# MSP-EXP430FR5739_1_1_4.net
KiCad netlist of a schematic drawn in EAGLE
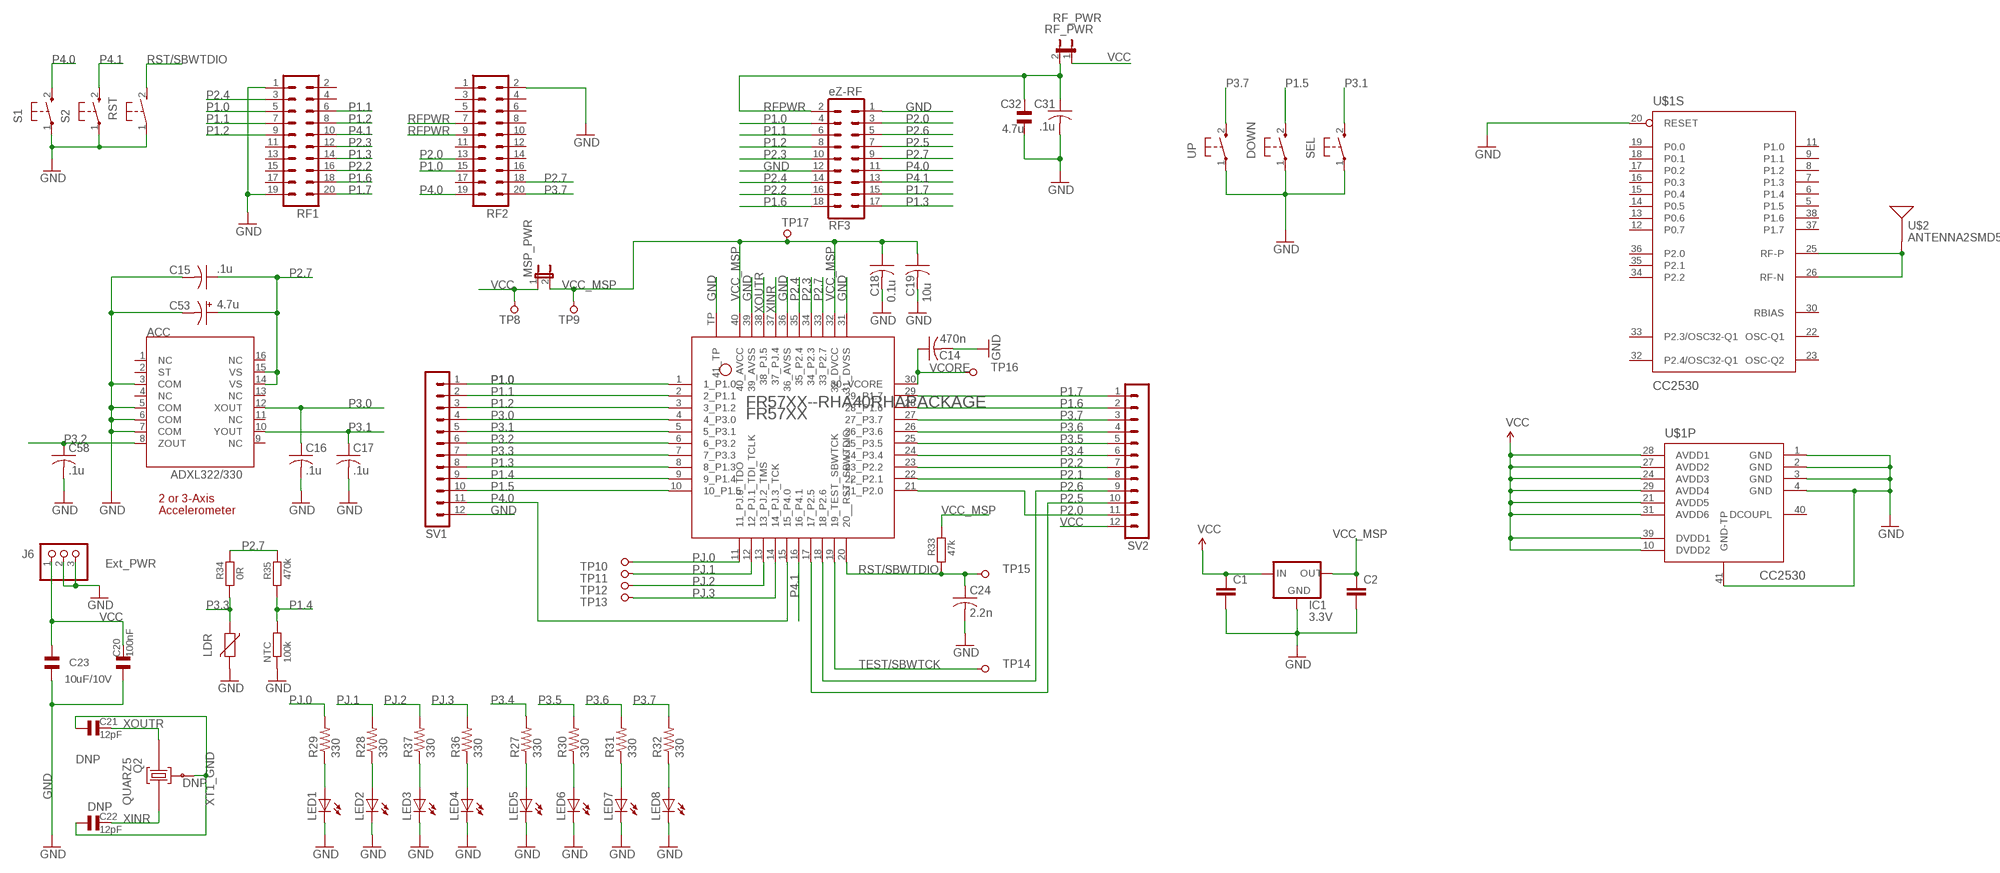
[diagram p0: schematic, sheet 1]

(export (version "E")
  (design (tool "Eeschema 10.0.6"))
  (components
    (comp (ref "ACC")
      (value "ADXL322/330")
      (footprint "eagle-import:RSA16")
      (libsource (lib "eagle-import") (part "ADXL330"))
    )
    (comp (ref "C1")
      (value "CAPPTH1")
      (footprint "eagle-import:CAP-PTH-5MM")
      (libsource (lib "eagle-import") (part "CAPPTH1"))
    )
    (comp (ref "C2")
      (value "CAPPTH1")
      (footprint "eagle-import:CAP-PTH-5MM")
      (libsource (lib "eagle-import") (part "CAPPTH1"))
    )
    (comp (ref "C14")
      (value "470n")
      (footprint "eagle-import:C0603")
      (libsource (lib "eagle-import") (part "C-USC0603"))
    )
    (comp (ref "C15")
      (value ".1u")
      (footprint "eagle-import:C0603")
      (libsource (lib "eagle-import") (part "C-USC0603"))
    )
    (comp (ref "C16")
      (value ".1u")
      (footprint "eagle-import:C0603")
      (libsource (lib "eagle-import") (part "C-USC0603"))
    )
    (comp (ref "C17")
      (value ".1u")
      (footprint "eagle-import:C0603")
      (libsource (lib "eagle-import") (part "C-USC0603"))
    )
    (comp (ref "C18")
      (value "0.1u")
      (footprint "eagle-import:C0603")
      (libsource (lib "eagle-import") (part "C-USC0603"))
    )
    (comp (ref "C19")
      (value "10u")
      (footprint "eagle-import:C0603")
      (libsource (lib "eagle-import") (part "C-USC0603"))
    )
    (comp (ref "C20")
      (value "100nF")
      (footprint "eagle-import:0603")
      (libsource (lib "eagle-import") (part "C_SMD0603"))
    )
    (comp (ref "C21")
      (value "12pF")
      (footprint "eagle-import:0603")
      (libsource (lib "eagle-import") (part "C_SMD0603"))
    )
    (comp (ref "C22")
      (value "12pF")
      (footprint "eagle-import:0603")
      (libsource (lib "eagle-import") (part "C_SMD0603"))
    )
    (comp (ref "C23")
      (value "10uF/10V")
      (footprint "eagle-import:0805")
      (libsource (lib "eagle-import") (part "C_0805"))
    )
    (comp (ref "C24")
      (value "2.2n")
      (footprint "eagle-import:C0603")
      (libsource (lib "eagle-import") (part "C-USC0603"))
    )
    (comp (ref "C31")
      (value ".1u")
      (footprint "eagle-import:C0603")
      (libsource (lib "eagle-import") (part "C-USC0603"))
    )
    (comp (ref "C32")
      (value "4.7u")
      (footprint "eagle-import:CSMD0805")
      (libsource (lib "eagle-import") (part "CSMD0805"))
    )
    (comp (ref "C53")
      (value "4.7u")
      (footprint "eagle-import:SMC_A")
      (libsource (lib "eagle-import") (part "CPOL-USSMCA"))
    )
    (comp (ref "C58")
      (value ".1u")
      (footprint "eagle-import:C0603")
      (libsource (lib "eagle-import") (part "C-USC0603"))
    )
    (comp (ref "DOWN")
      (value "PB")
      (footprint "eagle-import:PBTH")
      (libsource (lib "eagle-import") (part "PB"))
    )
    (comp (ref "FR57XX")
      (value "FR57XX--RHA40RHAPACKAGE")
      (footprint "eagle-import:RHA40")
      (libsource (lib "eagle-import") (part "FR57XX--RHA40RHAPACKAGE"))
    )
    (comp (ref "IC1")
      (value "3.3V")
      (footprint "eagle-import:78LXX")
      (libsource (lib "eagle-import") (part "78LXX"))
    )
    (comp (ref "J6")
      (value "PINHD-1X3")
      (footprint "eagle-import:1X03")
      (libsource (lib "eagle-import") (part "PINHD-1X3"))
    )
    (comp (ref "LDR")
      (value "R3,4")
      (footprint "eagle-import:R-3,4")
      (libsource (lib "eagle-import") (part "R3,4"))
    )
    (comp (ref "LED1")
      (value "LEDCHIPLED_0603")
      (footprint "eagle-import:CHIPLED_0603")
      (libsource (lib "eagle-import") (part "LEDCHIPLED_0603"))
    )
    (comp (ref "LED2")
      (value "LEDCHIPLED_0603")
      (footprint "eagle-import:CHIPLED_0603")
      (libsource (lib "eagle-import") (part "LEDCHIPLED_0603"))
    )
    (comp (ref "LED3")
      (value "LEDCHIPLED_0603")
      (footprint "eagle-import:CHIPLED_0603")
      (libsource (lib "eagle-import") (part "LEDCHIPLED_0603"))
    )
    (comp (ref "LED4")
      (value "LEDCHIPLED_0603")
      (footprint "eagle-import:CHIPLED_0603")
      (libsource (lib "eagle-import") (part "LEDCHIPLED_0603"))
    )
    (comp (ref "LED5")
      (value "LEDCHIPLED_0603")
      (footprint "eagle-import:CHIPLED_0603")
      (libsource (lib "eagle-import") (part "LEDCHIPLED_0603"))
    )
    (comp (ref "LED6")
      (value "LEDCHIPLED_0603")
      (footprint "eagle-import:CHIPLED_0603")
      (libsource (lib "eagle-import") (part "LEDCHIPLED_0603"))
    )
    (comp (ref "LED7")
      (value "LEDCHIPLED_0603")
      (footprint "eagle-import:CHIPLED_0603")
      (libsource (lib "eagle-import") (part "LEDCHIPLED_0603"))
    )
    (comp (ref "LED8")
      (value "LEDCHIPLED_0603")
      (footprint "eagle-import:CHIPLED_0603")
      (libsource (lib "eagle-import") (part "LEDCHIPLED_0603"))
    )
    (comp (ref "MSP_PWR")
      (value "JP1E")
      (footprint "eagle-import:JP1")
      (libsource (lib "eagle-import") (part "JP1E"))
    )
    (comp (ref "NTC")
      (value "100k")
      (footprint "eagle-import:0805")
      (libsource (lib "eagle-import") (part "R_0805"))
    )
    (comp (ref "Q2")
      (value "QUARZ5")
      (footprint "eagle-import:QUARZ5")
      (libsource (lib "eagle-import") (part "QUARZ5"))
    )
    (comp (ref "R27")
      (value "330")
      (footprint "eagle-import:R0603")
      (libsource (lib "eagle-import") (part "R-US_R0603"))
    )
    (comp (ref "R28")
      (value "330")
      (footprint "eagle-import:R0603")
      (libsource (lib "eagle-import") (part "R-US_R0603"))
    )
    (comp (ref "R29")
      (value "330")
      (footprint "eagle-import:R0603")
      (libsource (lib "eagle-import") (part "R-US_R0603"))
    )
    (comp (ref "R30")
      (value "330")
      (footprint "eagle-import:R0603")
      (libsource (lib "eagle-import") (part "R-US_R0603"))
    )
    (comp (ref "R31")
      (value "330")
      (footprint "eagle-import:R0603")
      (libsource (lib "eagle-import") (part "R-US_R0603"))
    )
    (comp (ref "R32")
      (value "330")
      (footprint "eagle-import:R0603")
      (libsource (lib "eagle-import") (part "R-US_R0603"))
    )
    (comp (ref "R33")
      (value "47k")
      (footprint "eagle-import:0603")
      (libsource (lib "eagle-import") (part "R_SMDR0603"))
    )
    (comp (ref "R34")
      (value "0R")
      (footprint "eagle-import:0603")
      (libsource (lib "eagle-import") (part "R_SMDR0603"))
    )
    (comp (ref "R35")
      (value "470k")
      (footprint "eagle-import:0603")
      (libsource (lib "eagle-import") (part "R_SMDR0603"))
    )
    (comp (ref "R36")
      (value "330")
      (footprint "eagle-import:R0603")
      (libsource (lib "eagle-import") (part "R-US_R0603"))
    )
    (comp (ref "R37")
      (value "330")
      (footprint "eagle-import:R0603")
      (libsource (lib "eagle-import") (part "R-US_R0603"))
    )
    (comp (ref "RF1")
      (value "TFM-110-02-SM-D-A-K")
      (footprint "eagle-import:TFM-110-02-SM-D-A-K")
      (libsource (lib "eagle-import") (part "TFM-110-02-SM-D-A-K"))
    )
    (comp (ref "RF2")
      (value "TFM-110-02-SM-D-A-K")
      (footprint "eagle-import:TFM-110-02-SM-D-A-K")
      (libsource (lib "eagle-import") (part "TFM-110-02-SM-D-A-K"))
    )
    (comp (ref "RF3")
      (value "eZ-RF")
      (footprint "eagle-import:MA09-2")
      (libsource (lib "eagle-import") (part "MA09-2"))
    )
    (comp (ref "RF_PWR")
      (value "RF_PWR")
      (footprint "eagle-import:JP1")
      (libsource (lib "eagle-import") (part "JP1E"))
    )
    (comp (ref "RST")
      (value "EVQPPDASTD")
      (footprint "eagle-import:EVQPPDA")
      (libsource (lib "eagle-import") (part "EVQPPDASTD"))
    )
    (comp (ref "S1")
      (value "PB")
      (footprint "eagle-import:PBTH")
      (libsource (lib "eagle-import") (part "PB"))
    )
    (comp (ref "S2")
      (value "PB")
      (footprint "eagle-import:PBTH")
      (libsource (lib "eagle-import") (part "PB"))
    )
    (comp (ref "SEL")
      (value "PB")
      (footprint "eagle-import:PBTH")
      (libsource (lib "eagle-import") (part "PB"))
    )
    (comp (ref "SV1")
      (value "MA12-1")
      (footprint "eagle-import:MA12-1")
      (libsource (lib "eagle-import") (part "MA12-1"))
    )
    (comp (ref "SV2")
      (value "MA12-1")
      (footprint "eagle-import:MA12-1")
      (libsource (lib "eagle-import") (part "MA12-1"))
    )
    (comp (ref "TP8")
      (value "TP05TP10")
      (footprint "eagle-import:TP10")
      (libsource (lib "eagle-import") (part "TP05TP10"))
    )
    (comp (ref "TP9")
      (value "TP05TP10")
      (footprint "eagle-import:TP10")
      (libsource (lib "eagle-import") (part "TP05TP10"))
    )
    (comp (ref "TP10")
      (value "TP05TP10")
      (footprint "eagle-import:TP10")
      (libsource (lib "eagle-import") (part "TP05TP10"))
    )
    (comp (ref "TP11")
      (value "TP05TP10")
      (footprint "eagle-import:TP10")
      (libsource (lib "eagle-import") (part "TP05TP10"))
    )
    (comp (ref "TP12")
      (value "TP05TP10")
      (footprint "eagle-import:TP10")
      (libsource (lib "eagle-import") (part "TP05TP10"))
    )
    (comp (ref "TP13")
      (value "TP05TP10")
      (footprint "eagle-import:TP10")
      (libsource (lib "eagle-import") (part "TP05TP10"))
    )
    (comp (ref "TP14")
      (value "TP05TP10")
      (footprint "eagle-import:TP10")
      (libsource (lib "eagle-import") (part "TP05TP10"))
    )
    (comp (ref "TP15")
      (value "TP05TP10")
      (footprint "eagle-import:TP10")
      (libsource (lib "eagle-import") (part "TP05TP10"))
    )
    (comp (ref "TP16")
      (value "TP05TP10")
      (footprint "eagle-import:TP10")
      (libsource (lib "eagle-import") (part "TP05TP10"))
    )
    (comp (ref "TP17")
      (value "TP05TP10")
      (footprint "eagle-import:TP10")
      (libsource (lib "eagle-import") (part "TP05TP10"))
    )
    (comp (ref "U$1")
      (value "CC2530")
      (footprint "eagle-import:QFN50P600X600X100-41N")
      (libsource (lib "eagle-import") (part "CC2530"))
    )
    (comp (ref "U$2")
      (value "ANTENNA2SMD5")
      (footprint "eagle-import:ANTENNA-CHIP5")
      (libsource (lib "eagle-import") (part "ANTENNA2SMD5"))
    )
    (comp (ref "UP")
      (value "PB")
      (footprint "eagle-import:PBTH")
      (libsource (lib "eagle-import") (part "PB"))
    )
  )
  (nets
    (net (code "1") (name "/DCOUPL") (class "Default")
      (node (ref "U$1") (pin "40") (pinfunction "DCOUPL_40") (pintype "power_in"))
    )
    (net (code "2") (name "/P1.0") (class "Default")
      (node (ref "FR57XX") (pin "1") (pinfunction "1_P1.0_1") (pintype "passive"))
      (node (ref "RF1") (pin "5") (pinfunction "5_5") (pintype "passive"))
      (node (ref "RF2") (pin "15") (pinfunction "15_15") (pintype "passive"))
      (node (ref "RF3") (pin "4") (pinfunction "4_4") (pintype "passive"))
      (node (ref "SV1") (pin "1") (pinfunction "1_1") (pintype "passive"))
    )
    (net (code "3") (name "/P1.1") (class "Default")
      (node (ref "FR57XX") (pin "2") (pinfunction "2_P1.1_2") (pintype "passive"))
      (node (ref "RF1") (pin "6") (pinfunction "6_6") (pintype "passive"))
      (node (ref "RF1") (pin "7") (pinfunction "7_7") (pintype "passive"))
      (node (ref "RF3") (pin "6") (pinfunction "6_6") (pintype "passive"))
      (node (ref "SV1") (pin "2") (pinfunction "2_2") (pintype "passive"))
    )
    (net (code "4") (name "/P1.2") (class "Default")
      (node (ref "FR57XX") (pin "3") (pinfunction "3_P1.2_3") (pintype "passive"))
      (node (ref "RF1") (pin "8") (pinfunction "8_8") (pintype "passive"))
      (node (ref "RF1") (pin "9") (pinfunction "9_9") (pintype "passive"))
      (node (ref "RF3") (pin "8") (pinfunction "8_8") (pintype "passive"))
      (node (ref "SV1") (pin "3") (pinfunction "3_3") (pintype "passive"))
    )
    (net (code "5") (name "/P1.3") (class "Default")
      (node (ref "FR57XX") (pin "8") (pinfunction "8_P1.3_8") (pintype "passive"))
      (node (ref "RF1") (pin "14") (pinfunction "14_14") (pintype "passive"))
      (node (ref "RF3") (pin "17") (pinfunction "17_17") (pintype "passive"))
      (node (ref "SV1") (pin "8") (pinfunction "8_8") (pintype "passive"))
    )
    (net (code "6") (name "/P1.4") (class "Default")
      (node (ref "FR57XX") (pin "9") (pinfunction "9_P1.4_9") (pintype "passive"))
      (node (ref "NTC") (pin "2") (pinfunction "2_2") (pintype "passive"))
      (node (ref "R35") (pin "1") (pinfunction "1_1") (pintype "passive"))
      (node (ref "SV1") (pin "9") (pinfunction "9_9") (pintype "passive"))
    )
    (net (code "7") (name "/P1.5") (class "Default")
      (node (ref "DOWN") (pin "2") (pinfunction "S_2") (pintype "passive"))
      (node (ref "FR57XX") (pin "10") (pinfunction "10_P1.5_10") (pintype "passive"))
      (node (ref "SV1") (pin "10") (pinfunction "10_10") (pintype "passive"))
    )
    (net (code "8") (name "/P1.6") (class "Default")
      (node (ref "FR57XX") (pin "28") (pinfunction "28_P1.6_28") (pintype "passive"))
      (node (ref "RF1") (pin "18") (pinfunction "18_18") (pintype "passive"))
      (node (ref "RF3") (pin "18") (pinfunction "18_18") (pintype "passive"))
      (node (ref "SV2") (pin "2") (pinfunction "2_2") (pintype "passive"))
    )
    (net (code "9") (name "/P1.7") (class "Default")
      (node (ref "FR57XX") (pin "29") (pinfunction "29_P1.7_29") (pintype "passive"))
      (node (ref "RF1") (pin "20") (pinfunction "20_20") (pintype "passive"))
      (node (ref "RF3") (pin "15") (pinfunction "15_15") (pintype "passive"))
      (node (ref "SV2") (pin "1") (pinfunction "1_1") (pintype "passive"))
    )
    (net (code "10") (name "/P2.0") (class "Default")
      (node (ref "FR57XX") (pin "21") (pinfunction "21_P2.0_21") (pintype "passive"))
      (node (ref "RF2") (pin "13") (pinfunction "13_13") (pintype "passive"))
      (node (ref "RF3") (pin "3") (pinfunction "3_3") (pintype "passive"))
      (node (ref "SV2") (pin "11") (pinfunction "11_11") (pintype "passive"))
    )
    (net (code "11") (name "/P2.1") (class "Default")
      (node (ref "FR57XX") (pin "22") (pinfunction "22_P2.1_22") (pintype "passive"))
      (node (ref "SV2") (pin "8") (pinfunction "8_8") (pintype "passive"))
    )
    (net (code "12") (name "/P2.2") (class "Default")
      (node (ref "FR57XX") (pin "23") (pinfunction "23_P2.2_23") (pintype "passive"))
      (node (ref "RF1") (pin "16") (pinfunction "16_16") (pintype "passive"))
      (node (ref "RF3") (pin "16") (pinfunction "16_16") (pintype "passive"))
      (node (ref "SV2") (pin "7") (pinfunction "7_7") (pintype "passive"))
    )
    (net (code "13") (name "/P2.3") (class "Default")
      (node (ref "FR57XX") (pin "34") (pinfunction "34_P2.3_34") (pintype "passive"))
      (node (ref "RF1") (pin "12") (pinfunction "12_12") (pintype "passive"))
      (node (ref "RF3") (pin "10") (pinfunction "10_10") (pintype "passive"))
    )
    (net (code "14") (name "/P2.4") (class "Default")
      (node (ref "FR57XX") (pin "35") (pinfunction "35_P2.4_35") (pintype "passive"))
      (node (ref "RF1") (pin "3") (pinfunction "3_3") (pintype "passive"))
      (node (ref "RF3") (pin "14") (pinfunction "14_14") (pintype "passive"))
    )
    (net (code "15") (name "/P2.5") (class "Default")
      (node (ref "FR57XX") (pin "17") (pinfunction "17_P2.5_17") (pintype "passive"))
      (node (ref "RF3") (pin "7") (pinfunction "7_7") (pintype "passive"))
      (node (ref "SV2") (pin "10") (pinfunction "10_10") (pintype "passive"))
    )
    (net (code "16") (name "/P2.6") (class "Default")
      (node (ref "FR57XX") (pin "18") (pinfunction "18_P2.6_18") (pintype "passive"))
      (node (ref "RF3") (pin "5") (pinfunction "5_5") (pintype "passive"))
      (node (ref "SV2") (pin "9") (pinfunction "9_9") (pintype "passive"))
    )
    (net (code "17") (name "/P2.7") (class "Default")
      (node (ref "ACC") (pin "14") (pinfunction "VS_14") (pintype "bidirectional"))
      (node (ref "ACC") (pin "15") (pinfunction "VS_15") (pintype "bidirectional"))
      (node (ref "C15") (pin "1") (pinfunction "1_1") (pintype "passive"))
      (node (ref "C53") (pin "+") (pinfunction "+_+") (pintype "passive"))
      (node (ref "FR57XX") (pin "33") (pinfunction "33_P2.7_33") (pintype "passive"))
      (node (ref "R34") (pin "2") (pinfunction "2_2") (pintype "passive"))
      (node (ref "R35") (pin "2") (pinfunction "2_2") (pintype "passive"))
      (node (ref "RF2") (pin "18") (pinfunction "18_18") (pintype "passive"))
      (node (ref "RF3") (pin "9") (pinfunction "9_9") (pintype "passive"))
    )
    (net (code "18") (name "/P3.0") (class "Default")
      (node (ref "ACC") (pin "12") (pinfunction "XOUT_12") (pintype "bidirectional"))
      (node (ref "C16") (pin "1") (pinfunction "1_1") (pintype "passive"))
      (node (ref "FR57XX") (pin "4") (pinfunction "4_P3.0_4") (pintype "passive"))
      (node (ref "SV1") (pin "4") (pinfunction "4_4") (pintype "passive"))
    )
    (net (code "19") (name "/P3.1") (class "Default")
      (node (ref "ACC") (pin "10") (pinfunction "YOUT_10") (pintype "bidirectional"))
      (node (ref "C17") (pin "1") (pinfunction "1_1") (pintype "passive"))
      (node (ref "FR57XX") (pin "5") (pinfunction "5_P3.1_5") (pintype "passive"))
      (node (ref "SEL") (pin "2") (pinfunction "S_2") (pintype "passive"))
      (node (ref "SV1") (pin "5") (pinfunction "5_5") (pintype "passive"))
    )
    (net (code "20") (name "/P3.2") (class "Default")
      (node (ref "ACC") (pin "8") (pinfunction "ZOUT_8") (pintype "bidirectional"))
      (node (ref "C58") (pin "1") (pinfunction "1_1") (pintype "passive"))
      (node (ref "FR57XX") (pin "6") (pinfunction "6_P3.2_6") (pintype "passive"))
      (node (ref "SV1") (pin "6") (pinfunction "6_6") (pintype "passive"))
    )
    (net (code "21") (name "/P3.3") (class "Default")
      (node (ref "FR57XX") (pin "7") (pinfunction "7_P3.3_7") (pintype "passive"))
      (node (ref "LDR") (pin "1") (pinfunction "1_1") (pintype "passive"))
      (node (ref "R34") (pin "1") (pinfunction "1_1") (pintype "passive"))
      (node (ref "SV1") (pin "7") (pinfunction "7_7") (pintype "passive"))
    )
    (net (code "22") (name "/P3.4") (class "Default")
      (node (ref "FR57XX") (pin "24") (pinfunction "24_P3.4_24") (pintype "passive"))
      (node (ref "R27") (pin "2") (pinfunction "2_2") (pintype "passive"))
      (node (ref "SV2") (pin "6") (pinfunction "6_6") (pintype "passive"))
    )
    (net (code "23") (name "/P3.5") (class "Default")
      (node (ref "FR57XX") (pin "25") (pinfunction "25_P3.5_25") (pintype "passive"))
      (node (ref "R30") (pin "2") (pinfunction "2_2") (pintype "passive"))
      (node (ref "SV2") (pin "5") (pinfunction "5_5") (pintype "passive"))
    )
    (net (code "24") (name "/P3.6") (class "Default")
      (node (ref "FR57XX") (pin "26") (pinfunction "26_P3.6_26") (pintype "passive"))
      (node (ref "R31") (pin "2") (pinfunction "2_2") (pintype "passive"))
      (node (ref "SV2") (pin "4") (pinfunction "4_4") (pintype "passive"))
    )
    (net (code "25") (name "/P3.7") (class "Default")
      (node (ref "FR57XX") (pin "27") (pinfunction "27_P3.7_27") (pintype "passive"))
      (node (ref "R32") (pin "2") (pinfunction "2_2") (pintype "passive"))
      (node (ref "RF2") (pin "20") (pinfunction "20_20") (pintype "passive"))
      (node (ref "SV2") (pin "3") (pinfunction "3_3") (pintype "passive"))
      (node (ref "UP") (pin "2") (pinfunction "S_2") (pintype "passive"))
    )
    (net (code "26") (name "/P4.0") (class "Default")
      (node (ref "FR57XX") (pin "15") (pinfunction "15_P4.0_15") (pintype "passive"))
      (node (ref "RF2") (pin "19") (pinfunction "19_19") (pintype "passive"))
      (node (ref "RF3") (pin "11") (pinfunction "11_11") (pintype "passive"))
      (node (ref "S1") (pin "2") (pinfunction "S_2") (pintype "passive"))
      (node (ref "SV1") (pin "11") (pinfunction "11_11") (pintype "passive"))
    )
    (net (code "27") (name "/P4.1") (class "Default")
      (node (ref "FR57XX") (pin "16") (pinfunction "16_P4.1_16") (pintype "passive"))
      (node (ref "RF1") (pin "10") (pinfunction "10_10") (pintype "passive"))
      (node (ref "RF3") (pin "13") (pinfunction "13_13") (pintype "passive"))
      (node (ref "S2") (pin "2") (pinfunction "S_2") (pintype "passive"))
    )
    (net (code "28") (name "/PJ.0") (class "Default")
      (node (ref "FR57XX") (pin "11") (pinfunction "11_PJ.0_TDO_11") (pintype "passive"))
      (node (ref "R29") (pin "2") (pinfunction "2_2") (pintype "passive"))
      (node (ref "TP10") (pin "1") (pinfunction "1_1") (pintype "passive"))
    )
    (net (code "29") (name "/PJ.1") (class "Default")
      (node (ref "FR57XX") (pin "12") (pinfunction "12_PJ.1_TDI_TCLK_12") (pintype "passive"))
      (node (ref "R28") (pin "2") (pinfunction "2_2") (pintype "passive"))
      (node (ref "TP11") (pin "1") (pinfunction "1_1") (pintype "passive"))
    )
    (net (code "30") (name "/PJ.2") (class "Default")
      (node (ref "FR57XX") (pin "13") (pinfunction "13_PJ.2_TMS_13") (pintype "passive"))
      (node (ref "R37") (pin "2") (pinfunction "2_2") (pintype "passive"))
      (node (ref "TP12") (pin "1") (pinfunction "1_1") (pintype "passive"))
    )
    (net (code "31") (name "/PJ.3") (class "Default")
      (node (ref "FR57XX") (pin "14") (pinfunction "14_PJ.3_TCK_14") (pintype "passive"))
      (node (ref "R36") (pin "2") (pinfunction "2_2") (pintype "passive"))
      (node (ref "TP13") (pin "1") (pinfunction "1_1") (pintype "passive"))
    )
    (net (code "32") (name "/RFPWR") (class "Default")
      (node (ref "C31") (pin "1") (pinfunction "1_1") (pintype "passive"))
      (node (ref "C32") (pin "1") (pinfunction "1_1") (pintype "passive"))
      (node (ref "RF2") (pin "7") (pinfunction "7_7") (pintype "passive"))
      (node (ref "RF2") (pin "9") (pinfunction "9_9") (pintype "passive"))
      (node (ref "RF3") (pin "2") (pinfunction "2_2") (pintype "passive"))
      (node (ref "RF_PWR") (pin "2") (pinfunction "2_2") (pintype "passive"))
    )
    (net (code "33") (name "/RST{slash}SBWTDIO") (class "Default")
      (node (ref "C24") (pin "1") (pinfunction "1_1") (pintype "passive"))
      (node (ref "FR57XX") (pin "20") (pinfunction "20__RST_SBWTDIO_20") (pintype "passive"))
      (node (ref "R33") (pin "1") (pinfunction "1_1") (pintype "passive"))
      (node (ref "RST") (pin "2") (pinfunction "S_2") (pintype "passive"))
      (node (ref "TP15") (pin "1") (pinfunction "1_1") (pintype "passive"))
    )
    (net (code "34") (name "/TEST{slash}SBWTCK") (class "Default")
      (node (ref "FR57XX") (pin "19") (pinfunction "19_TEST_SBWTCK_19") (pintype "passive"))
      (node (ref "TP14") (pin "1") (pinfunction "1_1") (pintype "passive"))
    )
    (net (code "35") (name "/VCC_MSP") (class "Default")
      (node (ref "C18") (pin "1") (pinfunction "1_1") (pintype "passive"))
      (node (ref "C19") (pin "1") (pinfunction "1_1") (pintype "passive"))
      (node (ref "C2") (pin "1") (pinfunction "1_1") (pintype "passive"))
      (node (ref "FR57XX") (pin "32") (pinfunction "32_DVCC_32") (pintype "passive"))
      (node (ref "FR57XX") (pin "40") (pinfunction "40_AVCC_40") (pintype "passive"))
      (node (ref "IC1") (pin "OUT") (pinfunction "OUT_OUT") (pintype "passive"))
      (node (ref "MSP_PWR") (pin "2") (pinfunction "2_2") (pintype "passive"))
      (node (ref "R33") (pin "2") (pinfunction "2_2") (pintype "passive"))
      (node (ref "TP17") (pin "1") (pinfunction "1_1") (pintype "passive"))
      (node (ref "TP9") (pin "1") (pinfunction "1_1") (pintype "passive"))
    )
    (net (code "36") (name "/VCORE") (class "Default")
      (node (ref "C14") (pin "1") (pinfunction "1_1") (pintype "passive"))
      (node (ref "FR57XX") (pin "30") (pinfunction "30_VCORE_30") (pintype "passive"))
      (node (ref "TP16") (pin "1") (pinfunction "1_1") (pintype "passive"))
    )
    (net (code "37") (name "/XINR") (class "Default")
      (node (ref "C22") (pin "2") (pinfunction "2_2") (pintype "passive"))
      (node (ref "FR57XX") (pin "37") (pinfunction "37_PJ.4_37") (pintype "passive"))
      (node (ref "Q2") (pin "1") (pinfunction "1_1") (pintype "passive"))
    )
    (net (code "38") (name "/XOUTR") (class "Default")
      (node (ref "C21") (pin "2") (pinfunction "2_2") (pintype "passive"))
      (node (ref "FR57XX") (pin "38") (pinfunction "38_PJ.5_38") (pintype "passive"))
      (node (ref "Q2") (pin "2") (pinfunction "2_2") (pintype "passive"))
    )
    (net (code "39") (name "/XT1_GND") (class "Default")
      (node (ref "C21") (pin "1") (pinfunction "1_1") (pintype "passive"))
      (node (ref "C22") (pin "1") (pinfunction "1_1") (pintype "passive"))
      (node (ref "Q2") (pin "GND@0") (pinfunction "0_GND@0") (pintype "passive"))
    )
    (net (code "40") (name "GND") (class "Default")
      (node (ref "ACC") (pin "3") (pinfunction "COM_3") (pintype "bidirectional"))
      (node (ref "ACC") (pin "5") (pinfunction "COM_5") (pintype "bidirectional"))
      (node (ref "ACC") (pin "6") (pinfunction "COM_6") (pintype "bidirectional"))
      (node (ref "ACC") (pin "7") (pinfunction "COM_7") (pintype "bidirectional"))
      (node (ref "C1") (pin "2") (pinfunction "2_2") (pintype "passive"))
      (node (ref "C14") (pin "2") (pinfunction "2_2") (pintype "passive"))
      (node (ref "C15") (pin "2") (pinfunction "2_2") (pintype "passive"))
      (node (ref "C16") (pin "2") (pinfunction "2_2") (pintype "passive"))
      (node (ref "C17") (pin "2") (pinfunction "2_2") (pintype "passive"))
      (node (ref "C18") (pin "2") (pinfunction "2_2") (pintype "passive"))
      (node (ref "C19") (pin "2") (pinfunction "2_2") (pintype "passive"))
      (node (ref "C2") (pin "2") (pinfunction "2_2") (pintype "passive"))
      (node (ref "C20") (pin "1") (pinfunction "1_1") (pintype "passive"))
      (node (ref "C23") (pin "1") (pinfunction "1_1") (pintype "passive"))
      (node (ref "C24") (pin "2") (pinfunction "2_2") (pintype "passive"))
      (node (ref "C31") (pin "2") (pinfunction "2_2") (pintype "passive"))
      (node (ref "C32") (pin "2") (pinfunction "2_2") (pintype "passive"))
      (node (ref "C53") (pin "-") (pinfunction "-_-") (pintype "passive"))
      (node (ref "C58") (pin "2") (pinfunction "2_2") (pintype "passive"))
      (node (ref "DOWN") (pin "1") (pinfunction "P_1") (pintype "passive"))
      (node (ref "FR57XX") (pin "31") (pinfunction "31_DVSS_31") (pintype "passive"))
      (node (ref "FR57XX") (pin "36") (pinfunction "36_AVSS_36") (pintype "passive"))
      (node (ref "FR57XX") (pin "39") (pinfunction "39_AVSS_39") (pintype "passive"))
      (node (ref "FR57XX") (pin "TP") (pinfunction "41_TP_TP") (pintype "passive"))
      (node (ref "IC1") (pin "GND") (pinfunction "GND_GND") (pintype "input"))
      (node (ref "J6") (pin "2") (pinfunction "2_2") (pintype "passive"))
      (node (ref "J6") (pin "3") (pinfunction "3_3") (pintype "passive"))
      (node (ref "LDR") (pin "2") (pinfunction "2_2") (pintype "passive"))
      (node (ref "LED1") (pin "C") (pinfunction "C_C") (pintype "passive"))
      (node (ref "LED2") (pin "C") (pinfunction "C_C") (pintype "passive"))
      (node (ref "LED3") (pin "C") (pinfunction "C_C") (pintype "passive"))
      (node (ref "LED4") (pin "C") (pinfunction "C_C") (pintype "passive"))
      (node (ref "LED5") (pin "C") (pinfunction "C_C") (pintype "passive"))
      (node (ref "LED6") (pin "C") (pinfunction "C_C") (pintype "passive"))
      (node (ref "LED7") (pin "C") (pinfunction "C_C") (pintype "passive"))
      (node (ref "LED8") (pin "C") (pinfunction "C_C") (pintype "passive"))
      (node (ref "NTC") (pin "1") (pinfunction "1_1") (pintype "passive"))
      (node (ref "RF1") (pin "1") (pinfunction "1_1") (pintype "passive"))
      (node (ref "RF1") (pin "19") (pinfunction "19_19") (pintype "passive"))
      (node (ref "RF2") (pin "2") (pinfunction "2_2") (pintype "passive"))
      (node (ref "RF3") (pin "1") (pinfunction "1_1") (pintype "passive"))
      (node (ref "RF3") (pin "12") (pinfunction "12_12") (pintype "passive"))
      (node (ref "RST") (pin "1") (pinfunction "P_1") (pintype "passive"))
      (node (ref "S1") (pin "1") (pinfunction "P_1") (pintype "passive"))
      (node (ref "S2") (pin "1") (pinfunction "P_1") (pintype "passive"))
      (node (ref "SEL") (pin "1") (pinfunction "P_1") (pintype "passive"))
      (node (ref "SV1") (pin "12") (pinfunction "12_12") (pintype "passive"))
      (node (ref "U$1") (pin "1") (pinfunction "GND_1") (pintype "power_in"))
      (node (ref "U$1") (pin "2") (pinfunction "GND_2") (pintype "power_in"))
      (node (ref "U$1") (pin "20") (pinfunction "RESET_20") (pintype "input"))
      (node (ref "U$1") (pin "3") (pinfunction "GND_3") (pintype "power_in"))
      (node (ref "U$1") (pin "4") (pinfunction "GND_4") (pintype "power_in"))
      (node (ref "U$1") (pin "41") (pinfunction "GND-TP_41") (pintype "power_in"))
      (node (ref "UP") (pin "1") (pinfunction "P_1") (pintype "passive"))
    )
    (net (code "41") (name "Net-(LED1-PadA)") (class "Default")
      (node (ref "LED1") (pin "A") (pinfunction "A_A") (pintype "passive"))
      (node (ref "R29") (pin "1") (pinfunction "1_1") (pintype "passive"))
    )
    (net (code "42") (name "Net-(LED2-PadA)") (class "Default")
      (node (ref "LED2") (pin "A") (pinfunction "A_A") (pintype "passive"))
      (node (ref "R28") (pin "1") (pinfunction "1_1") (pintype "passive"))
    )
    (net (code "43") (name "Net-(LED3-PadA)") (class "Default")
      (node (ref "LED3") (pin "A") (pinfunction "A_A") (pintype "passive"))
      (node (ref "R37") (pin "1") (pinfunction "1_1") (pintype "passive"))
    )
    (net (code "44") (name "Net-(LED4-PadA)") (class "Default")
      (node (ref "LED4") (pin "A") (pinfunction "A_A") (pintype "passive"))
      (node (ref "R36") (pin "1") (pinfunction "1_1") (pintype "passive"))
    )
    (net (code "45") (name "Net-(LED5-PadA)") (class "Default")
      (node (ref "LED5") (pin "A") (pinfunction "A_A") (pintype "passive"))
      (node (ref "R27") (pin "1") (pinfunction "1_1") (pintype "passive"))
    )
    (net (code "46") (name "Net-(LED6-PadA)") (class "Default")
      (node (ref "LED6") (pin "A") (pinfunction "A_A") (pintype "passive"))
      (node (ref "R30") (pin "1") (pinfunction "1_1") (pintype "passive"))
    )
    (net (code "47") (name "Net-(LED7-PadA)") (class "Default")
      (node (ref "LED7") (pin "A") (pinfunction "A_A") (pintype "passive"))
      (node (ref "R31") (pin "1") (pinfunction "1_1") (pintype "passive"))
    )
    (net (code "48") (name "Net-(LED8-PadA)") (class "Default")
      (node (ref "LED8") (pin "A") (pinfunction "A_A") (pintype "passive"))
      (node (ref "R32") (pin "1") (pinfunction "1_1") (pintype "passive"))
    )
    (net (code "49") (name "Net-(U$1B-RF-N)") (class "Default")
      (node (ref "U$1") (pin "25") (pinfunction "RF-P_25") (pintype "bidirectional"))
      (node (ref "U$1") (pin "26") (pinfunction "RF-N_26") (pintype "bidirectional"))
      (node (ref "U$2") (pin "FEED") (pinfunction "SIGNAL_FEED") (pintype "bidirectional"))
    )
    (net (code "50") (name "VCC") (class "Default")
      (node (ref "C1") (pin "1") (pinfunction "1_1") (pintype "passive"))
      (node (ref "C20") (pin "2") (pinfunction "2_2") (pintype "passive"))
      (node (ref "C23") (pin "2") (pinfunction "2_2") (pintype "passive"))
      (node (ref "IC1") (pin "IN") (pinfunction "IN_IN") (pintype "input"))
      (node (ref "J6") (pin "1") (pinfunction "1_1") (pintype "passive"))
      (node (ref "MSP_PWR") (pin "1") (pinfunction "1_1") (pintype "passive"))
      (node (ref "RF_PWR") (pin "1") (pinfunction "1_1") (pintype "passive"))
      (node (ref "SV2") (pin "12") (pinfunction "12_12") (pintype "passive"))
      (node (ref "TP8") (pin "1") (pinfunction "1_1") (pintype "passive"))
      (node (ref "U$1") (pin "10") (pinfunction "DVDD2_10") (pintype "power_in"))
      (node (ref "U$1") (pin "21") (pinfunction "AVDD5_21") (pintype "power_in"))
      (node (ref "U$1") (pin "24") (pinfunction "AVDD3_24") (pintype "power_in"))
      (node (ref "U$1") (pin "27") (pinfunction "AVDD2_27") (pintype "power_in"))
      (node (ref "U$1") (pin "28") (pinfunction "AVDD1_28") (pintype "power_in"))
      (node (ref "U$1") (pin "29") (pinfunction "AVDD4_29") (pintype "power_in"))
      (node (ref "U$1") (pin "31") (pinfunction "AVDD6_31") (pintype "power_in"))
      (node (ref "U$1") (pin "39") (pinfunction "DVDD1_39") (pintype "power_in"))
    )
    (net (code "51") (name "unconnected-(ACC-NC-Pad1)") (class "Default")
      (node (ref "ACC") (pin "1") (pinfunction "NC_1") (pintype "bidirectional"))
    )
    (net (code "52") (name "unconnected-(ACC-NC-Pad4)") (class "Default")
      (node (ref "ACC") (pin "4") (pinfunction "NC_4") (pintype "bidirectional"))
    )
    (net (code "53") (name "unconnected-(ACC-NC-Pad9)") (class "Default")
      (node (ref "ACC") (pin "9") (pinfunction "NC_9") (pintype "bidirectional"))
    )
    (net (code "54") (name "unconnected-(ACC-NC-Pad11)") (class "Default")
      (node (ref "ACC") (pin "11") (pinfunction "NC_11") (pintype "bidirectional"))
    )
    (net (code "55") (name "unconnected-(ACC-NC-Pad13)") (class "Default")
      (node (ref "ACC") (pin "13") (pinfunction "NC_13") (pintype "bidirectional"))
    )
    (net (code "56") (name "unconnected-(ACC-NC-Pad16)") (class "Default")
      (node (ref "ACC") (pin "16") (pinfunction "NC_16") (pintype "bidirectional"))
    )
    (net (code "57") (name "unconnected-(ACC-ST-Pad2)") (class "Default")
      (node (ref "ACC") (pin "2") (pinfunction "ST_2") (pintype "bidirectional"))
    )
    (net (code "58") (name "unconnected-(RF1-Pad2)") (class "Default")
      (node (ref "RF1") (pin "2") (pinfunction "2_2") (pintype "passive"))
    )
    (net (code "59") (name "unconnected-(RF1-Pad4)") (class "Default")
      (node (ref "RF1") (pin "4") (pinfunction "4_4") (pintype "passive"))
    )
    (net (code "60") (name "unconnected-(RF1-Pad11)") (class "Default")
      (node (ref "RF1") (pin "11") (pinfunction "11_11") (pintype "passive"))
    )
    (net (code "61") (name "unconnected-(RF1-Pad13)") (class "Default")
      (node (ref "RF1") (pin "13") (pinfunction "13_13") (pintype "passive"))
    )
    (net (code "62") (name "unconnected-(RF1-Pad15)") (class "Default")
      (node (ref "RF1") (pin "15") (pinfunction "15_15") (pintype "passive"))
    )
    (net (code "63") (name "unconnected-(RF1-Pad17)") (class "Default")
      (node (ref "RF1") (pin "17") (pinfunction "17_17") (pintype "passive"))
    )
    (net (code "64") (name "unconnected-(RF2-Pad1)") (class "Default")
      (node (ref "RF2") (pin "1") (pinfunction "1_1") (pintype "passive"))
    )
    (net (code "65") (name "unconnected-(RF2-Pad3)") (class "Default")
      (node (ref "RF2") (pin "3") (pinfunction "3_3") (pintype "passive"))
    )
    (net (code "66") (name "unconnected-(RF2-Pad4)") (class "Default")
      (node (ref "RF2") (pin "4") (pinfunction "4_4") (pintype "passive"))
    )
    (net (code "67") (name "unconnected-(RF2-Pad5)") (class "Default")
      (node (ref "RF2") (pin "5") (pinfunction "5_5") (pintype "passive"))
    )
    (net (code "68") (name "unconnected-(RF2-Pad6)") (class "Default")
      (node (ref "RF2") (pin "6") (pinfunction "6_6") (pintype "passive"))
    )
    (net (code "69") (name "unconnected-(RF2-Pad8)") (class "Default")
      (node (ref "RF2") (pin "8") (pinfunction "8_8") (pintype "passive"))
    )
    (net (code "70") (name "unconnected-(RF2-Pad10)") (class "Default")
      (node (ref "RF2") (pin "10") (pinfunction "10_10") (pintype "passive"))
    )
    (net (code "71") (name "unconnected-(RF2-Pad11)") (class "Default")
      (node (ref "RF2") (pin "11") (pinfunction "11_11") (pintype "passive"))
    )
    (net (code "72") (name "unconnected-(RF2-Pad12)") (class "Default")
      (node (ref "RF2") (pin "12") (pinfunction "12_12") (pintype "passive"))
    )
    (net (code "73") (name "unconnected-(RF2-Pad14)") (class "Default")
      (node (ref "RF2") (pin "14") (pinfunction "14_14") (pintype "passive"))
    )
    (net (code "74") (name "unconnected-(RF2-Pad16)") (class "Default")
      (node (ref "RF2") (pin "16") (pinfunction "16_16") (pintype "passive"))
    )
    (net (code "75") (name "unconnected-(RF2-Pad17)") (class "Default")
      (node (ref "RF2") (pin "17") (pinfunction "17_17") (pintype "passive"))
    )
    (net (code "76") (name "unconnected-(U$1B-OSC-Q1-Pad22)") (class "Default")
      (node (ref "U$1") (pin "22") (pinfunction "OSC-Q1_22") (pintype "bidirectional"))
    )
    (net (code "77") (name "unconnected-(U$1B-OSC-Q2-Pad23)") (class "Default")
      (node (ref "U$1") (pin "23") (pinfunction "OSC-Q2_23") (pintype "bidirectional"))
    )
    (net (code "78") (name "unconnected-(U$1B-P0.0-Pad19)") (class "Default")
      (node (ref "U$1") (pin "19") (pinfunction "P0.0_19") (pintype "bidirectional"))
    )
    (net (code "79") (name "unconnected-(U$1B-P0.1-Pad18)") (class "Default")
      (node (ref "U$1") (pin "18") (pinfunction "P0.1_18") (pintype "bidirectional"))
    )
    (net (code "80") (name "unconnected-(U$1B-P0.2-Pad17)") (class "Default")
      (node (ref "U$1") (pin "17") (pinfunction "P0.2_17") (pintype "bidirectional"))
    )
    (net (code "81") (name "unconnected-(U$1B-P0.3-Pad16)") (class "Default")
      (node (ref "U$1") (pin "16") (pinfunction "P0.3_16") (pintype "bidirectional"))
    )
    (net (code "82") (name "unconnected-(U$1B-P0.4-Pad15)") (class "Default")
      (node (ref "U$1") (pin "15") (pinfunction "P0.4_15") (pintype "bidirectional"))
    )
    (net (code "83") (name "unconnected-(U$1B-P0.5-Pad14)") (class "Default")
      (node (ref "U$1") (pin "14") (pinfunction "P0.5_14") (pintype "bidirectional"))
    )
    (net (code "84") (name "unconnected-(U$1B-P0.6-Pad13)") (class "Default")
      (node (ref "U$1") (pin "13") (pinfunction "P0.6_13") (pintype "bidirectional"))
    )
    (net (code "85") (name "unconnected-(U$1B-P0.7-Pad12)") (class "Default")
      (node (ref "U$1") (pin "12") (pinfunction "P0.7_12") (pintype "bidirectional"))
    )
    (net (code "86") (name "unconnected-(U$1B-P1.0-Pad11)") (class "Default")
      (node (ref "U$1") (pin "11") (pinfunction "P1.0_11") (pintype "bidirectional"))
    )
    (net (code "87") (name "unconnected-(U$1B-P1.1-Pad9)") (class "Default")
      (node (ref "U$1") (pin "9") (pinfunction "P1.1_9") (pintype "bidirectional"))
    )
    (net (code "88") (name "unconnected-(U$1B-P1.2-Pad8)") (class "Default")
      (node (ref "U$1") (pin "8") (pinfunction "P1.2_8") (pintype "bidirectional"))
    )
    (net (code "89") (name "unconnected-(U$1B-P1.3-Pad7)") (class "Default")
      (node (ref "U$1") (pin "7") (pinfunction "P1.3_7") (pintype "bidirectional"))
    )
    (net (code "90") (name "unconnected-(U$1B-P1.4-Pad6)") (class "Default")
      (node (ref "U$1") (pin "6") (pinfunction "P1.4_6") (pintype "bidirectional"))
    )
    (net (code "91") (name "unconnected-(U$1B-P1.5-Pad5)") (class "Default")
      (node (ref "U$1") (pin "5") (pinfunction "P1.5_5") (pintype "bidirectional"))
    )
    (net (code "92") (name "unconnected-(U$1B-P1.6-Pad38)") (class "Default")
      (node (ref "U$1") (pin "38") (pinfunction "P1.6_38") (pintype "bidirectional"))
    )
    (net (code "93") (name "unconnected-(U$1B-P1.7-Pad37)") (class "Default")
      (node (ref "U$1") (pin "37") (pinfunction "P1.7_37") (pintype "bidirectional"))
    )
    (net (code "94") (name "unconnected-(U$1B-P2.0-Pad36)") (class "Default")
      (node (ref "U$1") (pin "36") (pinfunction "P2.0_36") (pintype "bidirectional"))
    )
    (net (code "95") (name "unconnected-(U$1B-P2.1-Pad35)") (class "Default")
      (node (ref "U$1") (pin "35") (pinfunction "P2.1_35") (pintype "bidirectional"))
    )
    (net (code "96") (name "unconnected-(U$1B-P2.2-Pad34)") (class "Default")
      (node (ref "U$1") (pin "34") (pinfunction "P2.2_34") (pintype "bidirectional"))
    )
    (net (code "97") (name "unconnected-(U$1B-P2.3{slash}OSC32-Q1-Pad33)") (class "Default")
      (node (ref "U$1") (pin "33") (pinfunction "P2.3/OSC32-Q1_33") (pintype "bidirectional"))
    )
    (net (code "98") (name "unconnected-(U$1B-P2.4{slash}OSC32-Q1-Pad32)") (class "Default")
      (node (ref "U$1") (pin "32") (pinfunction "P2.4/OSC32-Q1_32") (pintype "bidirectional"))
    )
    (net (code "99") (name "unconnected-(U$1B-RBIAS-Pad30)") (class "Default")
      (node (ref "U$1") (pin "30") (pinfunction "RBIAS_30") (pintype "bidirectional"))
    )
  )
)
